# Boost_Converter_Circuit.net
KiCad netlist of a schematic drawn in Altium Designer
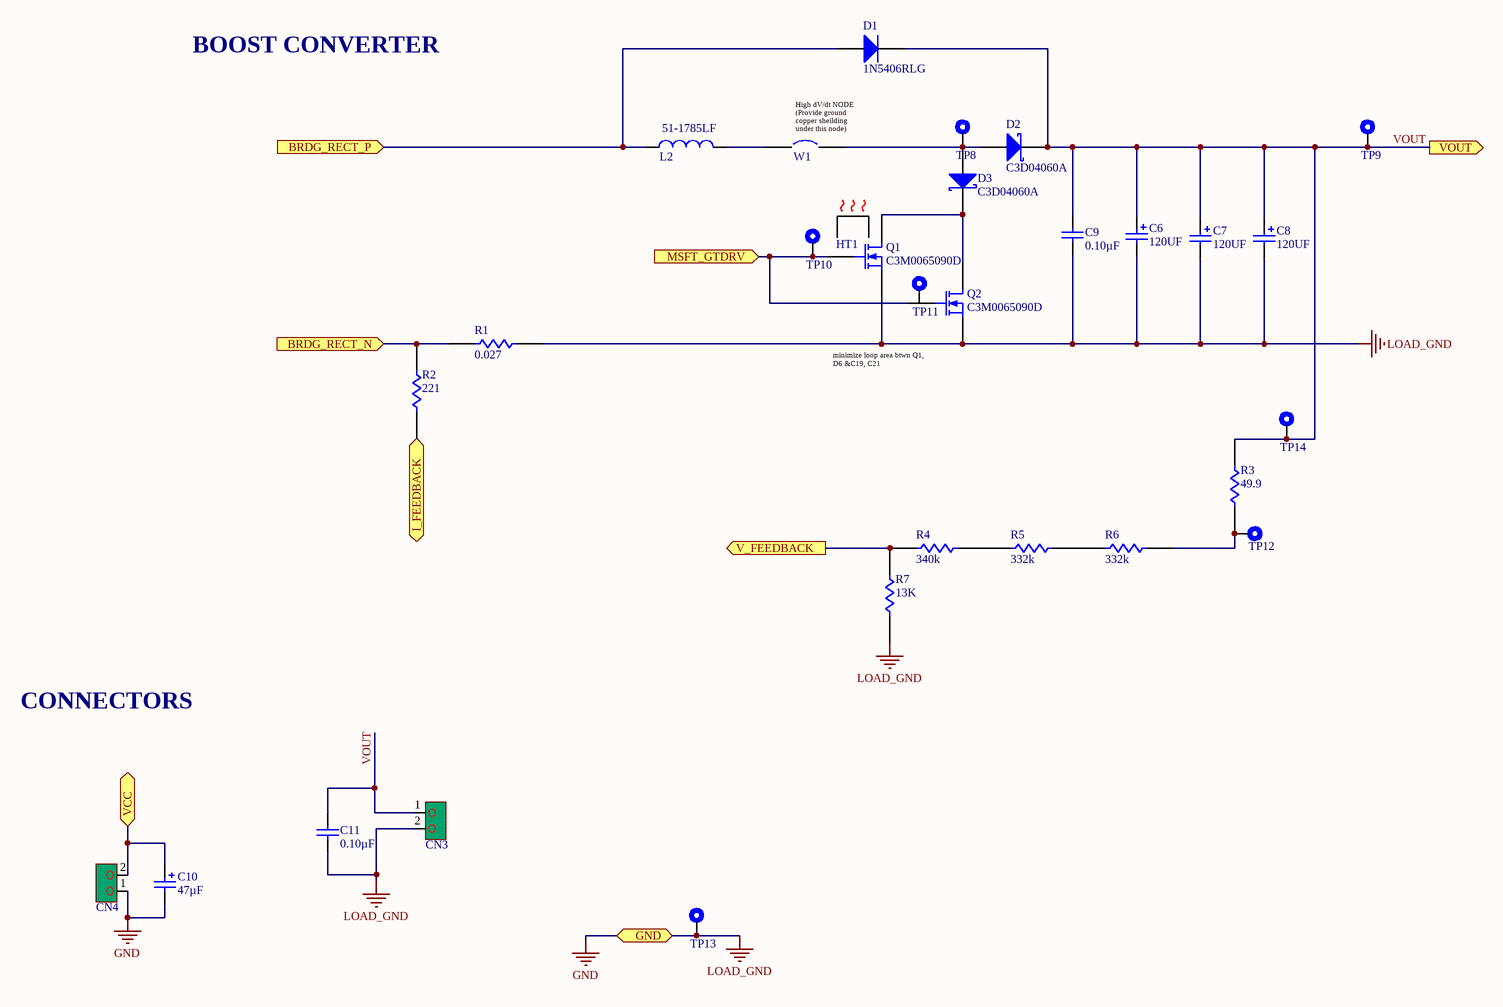
[diagram p0: Boost Converter Circuit.SchDoc]

(export (version "E")
  (design (tool "Eeschema 10.0.6"))
  (components
    (comp (ref "C6")
      (value "450QXW120MEFC18X31.5")
      (footprint "450QXW120MEFC18X31.5")
      (fields (field (name "CAPACITANCE") "120UF"))
      (libsource (lib "ucc28180") (part "450QXW120MEFC18X31.5"))
    )
    (comp (ref "C7")
      (value "450QXW120MEFC18X31.5")
      (footprint "450QXW120MEFC18X31.5")
      (fields (field (name "CAPACITANCE") "120UF"))
      (libsource (lib "ucc28180") (part "450QXW120MEFC18X31.5"))
    )
    (comp (ref "C8")
      (value "450QXW120MEFC18X31.5")
      (footprint "450QXW120MEFC18X31.5")
      (fields (field (name "CAPACITANCE") "120UF"))
      (libsource (lib "ucc28180") (part "450QXW120MEFC18X31.5"))
    )
    (comp (ref "C9")
      (value "GRM43DR72J104KW01L")
      (footprint "CAP1812")
      (description "CAP CER 0.1UF 630V X7R 1812")
      (fields (field (name "TOLERANCE") "±10%") (field (name "CAPACITANCE") "0.10µF"))
      (libsource (lib "ucc28180") (part "GRM43DR72J104KW01L"))
    )
    (comp (ref "C10")
      (value "ECA-1VM470")
      (footprint "CAPALUM47U")
      (description "CAP ALUM 47UF 20% 35V RADIAL")
      (fields (field (name "TOLERANCE") "±20%") (field (name "CAPACITANCE") "47µF"))
      (libsource (lib "ucc28180") (part "ECA-1VM470"))
    )
    (comp (ref "C11")
      (value "GRM43DR72J104KW01L")
      (footprint "CAP1812")
      (description "CAP CER 0.1UF 630V X7R 1812")
      (fields (field (name "TOLERANCE") "±10%") (field (name "CAPACITANCE") "0.10µF"))
      (libsource (lib "ucc28180") (part "GRM43DR72J104KW01L"))
    )
    (comp (ref "CN3")
      (value "1935776")
      (footprint "CONN_1935776")
      (description "CONN TERM BLOCK 2POS 5.0MM")
      (fields (field (name "VOLTAGE") "300V"))
      (libsource (lib "ucc28180") (part "1935776"))
    )
    (comp (ref "CN4")
      (value "1935776")
      (footprint "CONN_1935776")
      (description "CONN TERM BLOCK 2POS 5.0MM")
      (fields (field (name "VOLTAGE") "300V"))
      (libsource (lib "") (part "1935776_1"))
    )
    (comp (ref "D1")
      (value "1N5406RLG")
      (footprint "1N5406-DO201AD")
      (description "DIODE GEN PURP 600V 3A DO201AD")
      (fields
        (field (name "MANUFACTURER") "ON Semiconductor")
        (field (name "MANUFACTURER PART NUMBER") "1N5406RLG")
      )
      (libsource (lib "ucc28180-V03") (part "1N5406RLG"))
    )
    (comp (ref "D2")
      (value "C3D04060A")
      (footprint "C3D04060A")
      (description "DIODE SCHOTTKY 600V 4A TO220-2")
      (fields (field (name "MANUFACTURER PART NUMBER 1") "C3D04060A"))
      (libsource (lib "ucc28180") (part "C3D04060A"))
    )
    (comp (ref "D3")
      (value "C3D04060A")
      (footprint "C3D04060A")
      (description "DIODE SCHOTTKY 600V 4A TO220-2")
      (fields (field (name "MANUFACTURER PART NUMBER 1") "C3D04060A"))
      (libsource (lib "ucc28180-V04") (part "C3D04060A"))
    )
    (comp (ref "HT1")
      (value "HT_78245")
      (footprint "HT-78245")
      (libsource (lib "ucc28180-V04") (part "HT_78245"))
    )
    (comp (ref "L2")
      (value "51-1785LF")
      (footprint "G-51-185LF")
      (fields (field (name "MANUFACTURER") "Gowanda Electronics"))
      (libsource (lib "ucc28180-V02") (part "51-1785LF"))
    )
    (comp (ref "Q1")
      (value "C3M0065090D")
      (footprint "TO-247-3")
      (description "MOSFET N-CH 900V 36A TO247-3")
      (fields (field (name "MANUFACTURER PART NUMBER 1") "C3M0065090D"))
      (libsource (lib "ucc28180-V04") (part "C3M0065090D"))
    )
    (comp (ref "Q2")
      (value "C3M0065090D")
      (footprint "TO-247-3")
      (description "MOSFET N-CH 900V 36A TO247-3")
      (fields (field (name "MANUFACTURER PART NUMBER 1") "C3M0065090D"))
      (libsource (lib "ucc28180-V04") (part "C3M0065090D"))
    )
    (comp (ref "R1")
      (value "CRCW2512R0.027")
      (footprint "RES2512")
      (fields (field (name "RESISTANCE") "0.027"))
      (libsource (lib "ucc28180") (part "CRCW2512R0.027"))
    )
    (comp (ref "R2")
      (value "RC0805FR-07221RL")
      (footprint "RES0805_New")
      (description "RES SMD 221 OHM 1% 1/8W 0805")
      (fields
        (field (name "MANUFACTURER") "Yageo")
        (field (name "TOLERANCE") "±1%")
        (field (name "RESISTANCE") "221")
      )
      (libsource (lib "ucc28180-V04") (part "RC0805FR-07221RL"))
    )
    (comp (ref "R3")
      (value "CRCW120649R9FKEA")
      (footprint "RES1206")
      (description "RES SMD 49.9 OHM 1% 1/4W 1206")
      (fields (field (name "TOLERANCE") "±1%") (field (name "RESISTANCE (OHMS)") "49.9"))
      (libsource (lib "ucc28180") (part "CRCW120649R9FKEA"))
    )
    (comp (ref "R4")
      (value "CRCW0805340KFKEA")
      (footprint "RES0805_New")
      (description "RES SMD 340K OHM 1% 1/8W 0805")
      (fields (field (name "TOLERANCE") "±1%") (field (name "RESISTANCE (OHMS)") "340k"))
      (libsource (lib "ucc28180") (part "CRCW0805340KFKEA"))
    )
    (comp (ref "R5")
      (value "CRCW0805332KFKEA")
      (footprint "RES0805_New")
      (description "RES SMD 332K OHM 1% 1/8W 0805")
      (fields (field (name "TOLERANCE") "±1%") (field (name "RESISTANCE (OHMS)") "332k"))
      (libsource (lib "ucc28180") (part "CRCW0805332KFKEA"))
    )
    (comp (ref "R6")
      (value "CRCW0805332KFKEA")
      (footprint "RES0805_New")
      (description "RES SMD 332K OHM 1% 1/8W 0805")
      (fields (field (name "TOLERANCE") "±1%") (field (name "RESISTANCE (OHMS)") "332k"))
      (libsource (lib "ucc28180") (part "CRCW0805332KFKEA"))
    )
    (comp (ref "R7")
      (value "RC0805FR-0713KL")
      (footprint "RES0805_New")
      (description "RES SMD 13K OHM 1% 1/8W 0805")
      (fields
        (field (name "MANUFACTURER") "Yageo")
        (field (name "TOLERANCE") "±1%")
        (field (name "RESISTANCE") "13K")
      )
      (libsource (lib "ucc28180-V04") (part "RC0805FR-0713KL"))
    )
    (comp (ref "TP8")
      (value "5006")
      (footprint "Test Point")
      (description "TEST POINT PC COMPACT .063\"D BLK")
      (libsource (lib "ucc28180") (part "5006"))
    )
    (comp (ref "TP9")
      (value "5006")
      (footprint "Test Point")
      (description "TEST POINT PC COMPACT .063\"D BLK")
      (libsource (lib "ucc28180") (part "5006"))
    )
    (comp (ref "TP10")
      (value "5006")
      (footprint "Test Point")
      (description "TEST POINT PC COMPACT .063\"D BLK")
      (libsource (lib "ucc28180") (part "5006"))
    )
    (comp (ref "TP11")
      (value "5006")
      (footprint "Test Point")
      (description "TEST POINT PC COMPACT .063\"D BLK")
      (libsource (lib "ucc28180-V04") (part "5006"))
    )
    (comp (ref "TP12")
      (value "5006")
      (footprint "Test Point")
      (description "TEST POINT PC COMPACT .063\"D BLK")
      (libsource (lib "ucc28180") (part "5006"))
    )
    (comp (ref "TP13")
      (value "5006")
      (footprint "Test Point")
      (description "TEST POINT PC COMPACT .063\"D BLK")
      (libsource (lib "ucc28180") (part "5006"))
    )
    (comp (ref "TP14")
      (value "5006")
      (footprint "Test Point")
      (description "TEST POINT PC COMPACT .063\"D BLK")
      (libsource (lib "ucc28180-V04") (part "5006"))
    )
    (comp (ref "W1")
      (value "Wire")
      (footprint "Current Sense Wire")
      (libsource (lib "ucc28180-V02") (part "Wire"))
    )
  )
  (nets
    (net (code "1") (name "/BRDG_RECT_N") (class "Default")
      (node (ref "R1") (pin "2") (pinfunction "2_2") (pintype "passive"))
      (node (ref "R2") (pin "1") (pinfunction "1_1") (pintype "passive"))
    )
    (net (code "2") (name "/BRDG_RECT_P") (class "Default")
      (node (ref "D1") (pin "2") (pinfunction "A_2") (pintype "passive"))
      (node (ref "L2") (pin "1") (pinfunction "1_1") (pintype "passive"))
    )
    (net (code "3") (name "/I_FEEDBACK") (class "Default")
      (node (ref "R2") (pin "2") (pinfunction "2_2") (pintype "passive"))
    )
    (net (code "4") (name "/MSFT_GTDRV") (class "Default")
      (node (ref "Q1") (pin "1") (pinfunction "G_1") (pintype "passive"))
      (node (ref "Q2") (pin "1") (pinfunction "G_1") (pintype "passive"))
      (node (ref "TP10") (pin "1") (pinfunction "1_1") (pintype "passive"))
    )
    (net (code "5") (name "/VCC") (class "Default")
      (node (ref "C10") (pin "1") (pinfunction "1_1") (pintype "passive"))
      (node (ref "CN4") (pin "2") (pintype "passive"))
    )
    (net (code "6") (name "/VOUT") (class "Default")
      (node (ref "C11") (pin "2") (pinfunction "2_2") (pintype "passive"))
      (node (ref "C6") (pin "1") (pinfunction "1_1") (pintype "passive"))
      (node (ref "C7") (pin "1") (pinfunction "1_1") (pintype "passive"))
      (node (ref "C8") (pin "1") (pinfunction "1_1") (pintype "passive"))
      (node (ref "C9") (pin "2") (pinfunction "2_2") (pintype "passive"))
      (node (ref "CN3") (pin "1") (pintype "passive"))
      (node (ref "D1") (pin "1") (pinfunction "K_1") (pintype "passive"))
      (node (ref "D2") (pin "1") (pinfunction "K_1") (pintype "passive"))
      (node (ref "R3") (pin "1") (pinfunction "1_1") (pintype "passive"))
      (node (ref "TP14") (pin "1") (pinfunction "1_1") (pintype "passive"))
      (node (ref "TP9") (pin "1") (pinfunction "1_1") (pintype "passive"))
    )
    (net (code "7") (name "/V_FEEDBACK") (class "Default")
      (node (ref "R4") (pin "2") (pinfunction "2_2") (pintype "passive"))
      (node (ref "R7") (pin "1") (pinfunction "1_1") (pintype "passive"))
    )
    (net (code "8") (name "GND") (class "Default")
      (node (ref "C10") (pin "2") (pinfunction "2_2") (pintype "passive"))
      (node (ref "C11") (pin "1") (pinfunction "1_1") (pintype "passive"))
      (node (ref "C6") (pin "2") (pinfunction "2_2") (pintype "passive"))
      (node (ref "C7") (pin "2") (pinfunction "2_2") (pintype "passive"))
      (node (ref "C8") (pin "2") (pinfunction "2_2") (pintype "passive"))
      (node (ref "C9") (pin "1") (pinfunction "1_1") (pintype "passive"))
      (node (ref "CN3") (pin "2") (pintype "passive"))
      (node (ref "CN4") (pin "1") (pintype "passive"))
      (node (ref "Q1") (pin "3") (pinfunction "S_3") (pintype "passive"))
      (node (ref "Q2") (pin "3") (pinfunction "S_3") (pintype "passive"))
      (node (ref "R1") (pin "1") (pinfunction "1_1") (pintype "passive"))
      (node (ref "R7") (pin "2") (pinfunction "2_2") (pintype "passive"))
      (node (ref "TP13") (pin "1") (pinfunction "1_1") (pintype "passive"))
    )
    (net (code "9") (name "Net-(D2-A)") (class "Default")
      (node (ref "D2") (pin "2") (pinfunction "A_2") (pintype "passive"))
      (node (ref "D3") (pin "2") (pinfunction "A_2") (pintype "passive"))
      (node (ref "TP8") (pin "1") (pinfunction "1_1") (pintype "passive"))
      (node (ref "W1") (pin "2") (pinfunction "2_2") (pintype "passive"))
    )
    (net (code "10") (name "Net-(D3-K)") (class "Default")
      (node (ref "D3") (pin "1") (pinfunction "K_1") (pintype "passive"))
      (node (ref "Q1") (pin "2") (pinfunction "D_2") (pintype "passive"))
      (node (ref "Q2") (pin "2") (pinfunction "D_2") (pintype "passive"))
    )
    (net (code "11") (name "Net-(L2-Pad2)") (class "Default")
      (node (ref "L2") (pin "2") (pinfunction "2_2") (pintype "passive"))
      (node (ref "W1") (pin "1") (pinfunction "1_1") (pintype "passive"))
    )
    (net (code "12") (name "Net-(R3-Pad2)") (class "Default")
      (node (ref "R3") (pin "2") (pinfunction "2_2") (pintype "passive"))
      (node (ref "R6") (pin "1") (pinfunction "1_1") (pintype "passive"))
      (node (ref "TP12") (pin "1") (pinfunction "1_1") (pintype "passive"))
    )
    (net (code "13") (name "Net-(R4-Pad1)") (class "Default")
      (node (ref "R4") (pin "1") (pinfunction "1_1") (pintype "passive"))
      (node (ref "R5") (pin "2") (pinfunction "2_2") (pintype "passive"))
    )
    (net (code "14") (name "Net-(R5-Pad1)") (class "Default")
      (node (ref "R5") (pin "1") (pinfunction "1_1") (pintype "passive"))
      (node (ref "R6") (pin "2") (pinfunction "2_2") (pintype "passive"))
    )
    (net (code "15") (name "unconnected-(TP11-Pad1)") (class "Default")
      (node (ref "TP11") (pin "1") (pinfunction "1_1") (pintype "passive"))
    )
  )
)
